# LEDs.net
KiCad netlist of a schematic drawn in Altium Designer
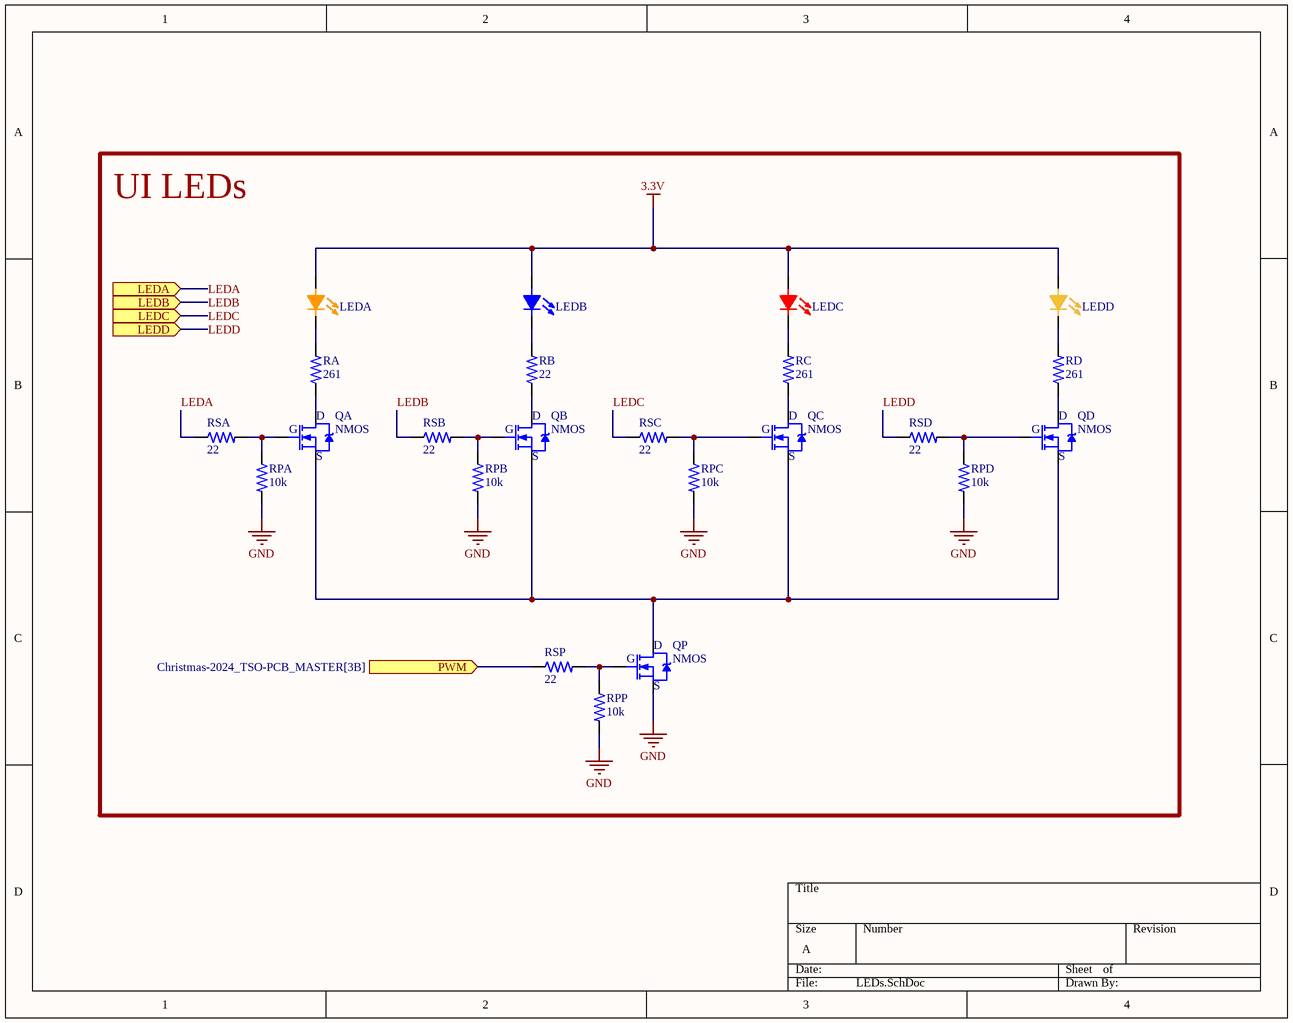
[diagram p0: LEDs.SchDoc]

(export (version "E")
  (design (tool "Eeschema 10.0.6"))
  (components
    (comp (ref "LEDA")
      (value "LED - ORANGE")
      (footprint "Christmas-2024_TSO-PCB:LED - 0603 - ORANGE")
      (description "LED, Orange, 0603")
      (fields (field (name "MFR") "Lite-On Inc."))
      (libsource (lib "Christmas-2024_TSO-PCB") (part "LED - ORANGE"))
    )
    (comp (ref "LEDB")
      (value "LED - BLUE")
      (footprint "Christmas-2024_TSO-PCB:LED - 0603 - BLUE")
      (description "LED, Blue, 0603")
      (fields (field (name "MFR") "Würth Elektronik"))
      (libsource (lib "Christmas-2024_TSO-PCB") (part "LED - BLUE"))
    )
    (comp (ref "LEDC")
      (value "LED - RED")
      (footprint "Christmas-2024_TSO-PCB:LED - 0603 - RED")
      (description "LED, Red, 0603")
      (fields (field (name "MFR") "Würth Elektronik"))
      (libsource (lib "Christmas-2024_TSO-PCB") (part "LED - RED"))
    )
    (comp (ref "LEDD")
      (value "LED - YELLOW")
      (footprint "Christmas-2024_TSO-PCB:LED - 0603")
      (description "LED, Yellow, 0603")
      (fields (field (name "MFR") "Würth Elektronik"))
      (libsource (lib "Christmas-2024_TSO-PCB") (part "LED - YELLOW"))
    )
    (comp (ref "QA")
      (value "NMOS")
      (footprint "Christmas-2024_TSO-PCB:SOT-23")
      (description "N-Channel MOSFET")
      (fields (field (name "MFR") "Diodes Incorporated"))
      (libsource (lib "Christmas-2024_TSO-PCB") (part "NMOS"))
    )
    (comp (ref "QB")
      (value "NMOS")
      (footprint "Christmas-2024_TSO-PCB:SOT-23")
      (description "N-Channel MOSFET")
      (fields (field (name "MFR") "Diodes Incorporated"))
      (libsource (lib "Christmas-2024_TSO-PCB") (part "NMOS"))
    )
    (comp (ref "QC")
      (value "NMOS")
      (footprint "Christmas-2024_TSO-PCB:SOT-23")
      (description "N-Channel MOSFET")
      (fields (field (name "MFR") "Diodes Incorporated"))
      (libsource (lib "Christmas-2024_TSO-PCB") (part "NMOS"))
    )
    (comp (ref "QD")
      (value "NMOS")
      (footprint "Christmas-2024_TSO-PCB:SOT-23")
      (description "N-Channel MOSFET")
      (fields (field (name "MFR") "Diodes Incorporated"))
      (libsource (lib "Christmas-2024_TSO-PCB") (part "NMOS"))
    )
    (comp (ref "QP")
      (value "NMOS")
      (footprint "Christmas-2024_TSO-PCB:SOT-23")
      (description "N-Channel MOSFET")
      (fields (field (name "MFR") "Diodes Incorporated"))
      (libsource (lib "Christmas-2024_TSO-PCB") (part "NMOS"))
    )
    (comp (ref "RA")
      (value "261")
      (footprint "Christmas-2024_TSO-PCB:0402R")
      (description "Resistor")
      (fields (field (name "MFR") "YAGEO") (field (name "Comment") "RES"))
      (libsource (lib "Christmas-2024_TSO-PCB") (part "RES"))
    )
    (comp (ref "RB")
      (value "22")
      (footprint "Christmas-2024_TSO-PCB:0402R")
      (description "Resistor")
      (fields (field (name "MFR") "YAGEO") (field (name "Comment") "RES"))
      (libsource (lib "Christmas-2024_TSO-PCB") (part "RES"))
    )
    (comp (ref "RC")
      (value "261")
      (footprint "Christmas-2024_TSO-PCB:0402R")
      (description "Resistor")
      (fields (field (name "MFR") "YAGEO") (field (name "Comment") "RES"))
      (libsource (lib "Christmas-2024_TSO-PCB") (part "RES"))
    )
    (comp (ref "RD")
      (value "261")
      (footprint "Christmas-2024_TSO-PCB:0402R")
      (description "Resistor")
      (fields (field (name "MFR") "YAGEO") (field (name "Comment") "RES"))
      (libsource (lib "Christmas-2024_TSO-PCB") (part "RES"))
    )
    (comp (ref "RPA")
      (value "10k")
      (footprint "Christmas-2024_TSO-PCB:0402R")
      (description "Resistor")
      (fields (field (name "MFR") "YAGEO") (field (name "Comment") "RES"))
      (libsource (lib "Christmas-2024_TSO-PCB") (part "RES"))
    )
    (comp (ref "RPB")
      (value "10k")
      (footprint "Christmas-2024_TSO-PCB:0402R")
      (description "Resistor")
      (fields (field (name "MFR") "YAGEO") (field (name "Comment") "RES"))
      (libsource (lib "Christmas-2024_TSO-PCB") (part "RES"))
    )
    (comp (ref "RPC")
      (value "10k")
      (footprint "Christmas-2024_TSO-PCB:0402R")
      (description "Resistor")
      (fields (field (name "MFR") "YAGEO") (field (name "Comment") "RES"))
      (libsource (lib "Christmas-2024_TSO-PCB") (part "RES"))
    )
    (comp (ref "RPD")
      (value "10k")
      (footprint "Christmas-2024_TSO-PCB:0402R")
      (description "Resistor")
      (fields (field (name "MFR") "YAGEO") (field (name "Comment") "RES"))
      (libsource (lib "Christmas-2024_TSO-PCB") (part "RES"))
    )
    (comp (ref "RPP")
      (value "10k")
      (footprint "Christmas-2024_TSO-PCB:0402R")
      (description "Resistor")
      (fields (field (name "MFR") "YAGEO") (field (name "Comment") "RES"))
      (libsource (lib "Christmas-2024_TSO-PCB") (part "RES"))
    )
    (comp (ref "RSA")
      (value "22")
      (footprint "Christmas-2024_TSO-PCB:0402R")
      (description "Resistor")
      (fields (field (name "MFR") "YAGEO") (field (name "Comment") "RES"))
      (libsource (lib "Christmas-2024_TSO-PCB") (part "RES"))
    )
    (comp (ref "RSB")
      (value "22")
      (footprint "Christmas-2024_TSO-PCB:0402R")
      (description "Resistor")
      (fields (field (name "MFR") "YAGEO") (field (name "Comment") "RES"))
      (libsource (lib "Christmas-2024_TSO-PCB") (part "RES"))
    )
    (comp (ref "RSC")
      (value "22")
      (footprint "Christmas-2024_TSO-PCB:0402R")
      (description "Resistor")
      (fields (field (name "MFR") "YAGEO") (field (name "Comment") "RES"))
      (libsource (lib "Christmas-2024_TSO-PCB") (part "RES"))
    )
    (comp (ref "RSD")
      (value "22")
      (footprint "Christmas-2024_TSO-PCB:0402R")
      (description "Resistor")
      (fields (field (name "MFR") "YAGEO") (field (name "Comment") "RES"))
      (libsource (lib "Christmas-2024_TSO-PCB") (part "RES"))
    )
    (comp (ref "RSP")
      (value "22")
      (footprint "Christmas-2024_TSO-PCB:0402R")
      (description "Resistor")
      (fields (field (name "MFR") "YAGEO") (field (name "Comment") "RES"))
      (libsource (lib "Christmas-2024_TSO-PCB") (part "RES"))
    )
  )
  (nets
    (net (code "1") (name "/LEDA") (class "Default")
      (node (ref "RSA") (pin "1") (pinfunction "1_1") (pintype "passive"))
    )
    (net (code "2") (name "/LEDB") (class "Default")
      (node (ref "RSB") (pin "1") (pinfunction "1_1") (pintype "passive"))
    )
    (net (code "3") (name "/LEDC") (class "Default")
      (node (ref "RSC") (pin "1") (pinfunction "1_1") (pintype "passive"))
    )
    (net (code "4") (name "/LEDD") (class "Default")
      (node (ref "RSD") (pin "1") (pinfunction "1_1") (pintype "passive"))
    )
    (net (code "5") (name "/PWM") (class "Default")
      (node (ref "RSP") (pin "1") (pinfunction "1_1") (pintype "passive"))
    )
    (net (code "6") (name "3.3V") (class "Default")
      (node (ref "LEDA") (pin "1") (pinfunction "A_1") (pintype "passive"))
      (node (ref "LEDB") (pin "1") (pinfunction "A_1") (pintype "passive"))
      (node (ref "LEDC") (pin "1") (pinfunction "A_1") (pintype "passive"))
      (node (ref "LEDD") (pin "1") (pinfunction "A_1") (pintype "passive"))
    )
    (net (code "7") (name "GND") (class "Default")
      (node (ref "QP") (pin "2") (pinfunction "S_2") (pintype "passive"))
      (node (ref "RPA") (pin "2") (pinfunction "2_2") (pintype "passive"))
      (node (ref "RPB") (pin "2") (pinfunction "2_2") (pintype "passive"))
      (node (ref "RPC") (pin "2") (pinfunction "2_2") (pintype "passive"))
      (node (ref "RPD") (pin "2") (pinfunction "2_2") (pintype "passive"))
      (node (ref "RPP") (pin "2") (pinfunction "2_2") (pintype "passive"))
    )
    (net (code "8") (name "Net-(LEDA-C)") (class "Default")
      (node (ref "LEDA") (pin "2") (pinfunction "C_2") (pintype "passive"))
      (node (ref "RA") (pin "2") (pinfunction "2_2") (pintype "passive"))
    )
    (net (code "9") (name "Net-(LEDB-C)") (class "Default")
      (node (ref "LEDB") (pin "2") (pinfunction "C_2") (pintype "passive"))
      (node (ref "RB") (pin "2") (pinfunction "2_2") (pintype "passive"))
    )
    (net (code "10") (name "Net-(LEDC-C)") (class "Default")
      (node (ref "LEDC") (pin "2") (pinfunction "C_2") (pintype "passive"))
      (node (ref "RC") (pin "2") (pinfunction "2_2") (pintype "passive"))
    )
    (net (code "11") (name "Net-(LEDD-C)") (class "Default")
      (node (ref "LEDD") (pin "2") (pinfunction "C_2") (pintype "passive"))
      (node (ref "RD") (pin "2") (pinfunction "2_2") (pintype "passive"))
    )
    (net (code "12") (name "Net-(QA-D)") (class "Default")
      (node (ref "QA") (pin "3") (pinfunction "D_3") (pintype "passive"))
      (node (ref "RA") (pin "1") (pinfunction "1_1") (pintype "passive"))
    )
    (net (code "13") (name "Net-(QA-G)") (class "Default")
      (node (ref "QA") (pin "1") (pinfunction "G_1") (pintype "passive"))
      (node (ref "RPA") (pin "1") (pinfunction "1_1") (pintype "passive"))
      (node (ref "RSA") (pin "2") (pinfunction "2_2") (pintype "passive"))
    )
    (net (code "14") (name "Net-(QA-S)") (class "Default")
      (node (ref "QA") (pin "2") (pinfunction "S_2") (pintype "passive"))
      (node (ref "QB") (pin "2") (pinfunction "S_2") (pintype "passive"))
      (node (ref "QC") (pin "2") (pinfunction "S_2") (pintype "passive"))
      (node (ref "QD") (pin "2") (pinfunction "S_2") (pintype "passive"))
      (node (ref "QP") (pin "3") (pinfunction "D_3") (pintype "passive"))
    )
    (net (code "15") (name "Net-(QB-D)") (class "Default")
      (node (ref "QB") (pin "3") (pinfunction "D_3") (pintype "passive"))
      (node (ref "RB") (pin "1") (pinfunction "1_1") (pintype "passive"))
    )
    (net (code "16") (name "Net-(QB-G)") (class "Default")
      (node (ref "QB") (pin "1") (pinfunction "G_1") (pintype "passive"))
      (node (ref "RPB") (pin "1") (pinfunction "1_1") (pintype "passive"))
      (node (ref "RSB") (pin "2") (pinfunction "2_2") (pintype "passive"))
    )
    (net (code "17") (name "Net-(QC-D)") (class "Default")
      (node (ref "QC") (pin "3") (pinfunction "D_3") (pintype "passive"))
      (node (ref "RC") (pin "1") (pinfunction "1_1") (pintype "passive"))
    )
    (net (code "18") (name "Net-(QC-G)") (class "Default")
      (node (ref "QC") (pin "1") (pinfunction "G_1") (pintype "passive"))
      (node (ref "RPC") (pin "1") (pinfunction "1_1") (pintype "passive"))
      (node (ref "RSC") (pin "2") (pinfunction "2_2") (pintype "passive"))
    )
    (net (code "19") (name "Net-(QD-D)") (class "Default")
      (node (ref "QD") (pin "3") (pinfunction "D_3") (pintype "passive"))
      (node (ref "RD") (pin "1") (pinfunction "1_1") (pintype "passive"))
    )
    (net (code "20") (name "Net-(QD-G)") (class "Default")
      (node (ref "QD") (pin "1") (pinfunction "G_1") (pintype "passive"))
      (node (ref "RPD") (pin "1") (pinfunction "1_1") (pintype "passive"))
      (node (ref "RSD") (pin "2") (pinfunction "2_2") (pintype "passive"))
    )
    (net (code "21") (name "Net-(QP-G)") (class "Default")
      (node (ref "QP") (pin "1") (pinfunction "G_1") (pintype "passive"))
      (node (ref "RPP") (pin "1") (pinfunction "1_1") (pintype "passive"))
      (node (ref "RSP") (pin "2") (pinfunction "2_2") (pintype "passive"))
    )
  )
)
